# FPGA_C.net
KiCad netlist of a schematic drawn in Altium Designer
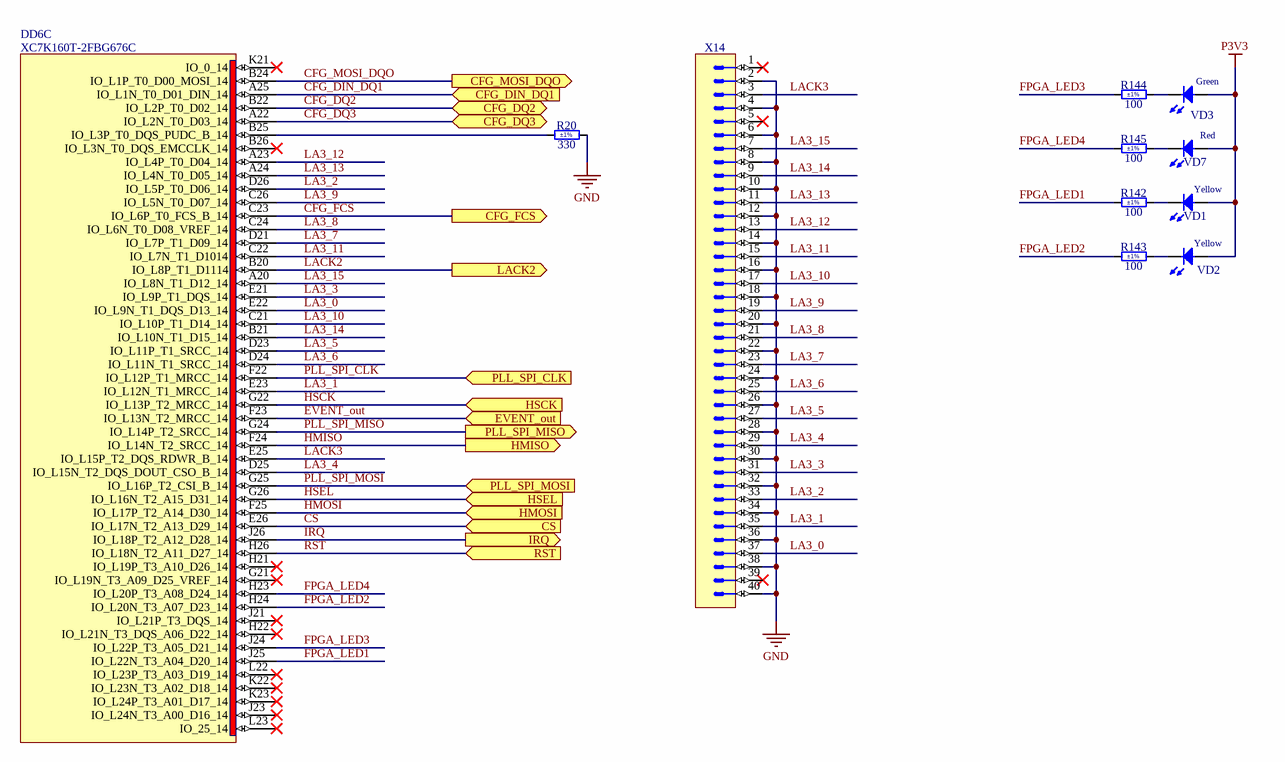
[diagram p0: FPGA_C.SchDoc]

(export (version "E")
  (design (tool "Eeschema 10.0.6"))
  (components
    (comp (ref "DD6")
      (value "XC7K160T-2FBG676C")
      (footprint "BGA676C100P26X26_2700X2700X254")
      (description "KINTEX-7, FPGA, 676-Ball BGA, Pb-Free")
      (fields (field (name "MANUFACTURER") "XILINX") (field (name "AUTHOR") "CERN DEM BC"))
      (libsource (lib "ICs And Semiconductors") (part "XC7K160T-xFBG676"))
    )
    (comp (ref "R20")
      (value "330")
      (footprint "RESC2012X60N")
      (description "Resistor - 1%")
      (fields
        (field (name "TOLERANCE") "±1%")
        (field (name "PART NUMBER") "R0805_330R_1%_0.125W_100PPM")
        (field (name "POWER") "0.125W")
        (field (name "AUTHOR") "CERN DEM JLC")
      )
      (libsource (lib "Resistors") (part "Resistor - 1%"))
    )
    (comp (ref "R142")
      (value "100")
      (footprint "RESC2012X60N")
      (description "Resistor - 1%")
      (fields
        (field (name "TOLERANCE") "±1%")
        (field (name "PART NUMBER") "R0805_100R_1%_0.125W_100PPM")
        (field (name "POWER") "0.125W")
        (field (name "AUTHOR") "CERN DEM JLC")
      )
      (libsource (lib "Resistors") (part "Resistor - 1%"))
    )
    (comp (ref "R143")
      (value "100")
      (footprint "RESC2012X60N")
      (description "Resistor - 1%")
      (fields
        (field (name "TOLERANCE") "±1%")
        (field (name "PART NUMBER") "R0805_100R_1%_0.125W_100PPM")
        (field (name "POWER") "0.125W")
        (field (name "AUTHOR") "CERN DEM JLC")
      )
      (libsource (lib "Resistors") (part "Resistor - 1%"))
    )
    (comp (ref "R144")
      (value "100")
      (footprint "RESC2012X60N")
      (description "Resistor - 1%")
      (fields
        (field (name "TOLERANCE") "±1%")
        (field (name "PART NUMBER") "R0805_100R_1%_0.125W_100PPM")
        (field (name "POWER") "0.125W")
        (field (name "AUTHOR") "CERN DEM JLC")
      )
      (libsource (lib "Resistors") (part "Resistor - 1%"))
    )
    (comp (ref "R145")
      (value "100")
      (footprint "RESC2012X60N")
      (description "Resistor - 1%")
      (fields
        (field (name "TOLERANCE") "±1%")
        (field (name "PART NUMBER") "R0805_100R_1%_0.125W_100PPM")
        (field (name "POWER") "0.125W")
        (field (name "AUTHOR") "CERN DEM JLC")
      )
      (libsource (lib "Resistors") (part "Resistor - 1%"))
    )
    (comp (ref "VD1")
      (value "Yellow")
      (footprint "LED_KINGBRIGHT_KPT-2012YC")
      (description "LED Yellow 1C 2A")
      (fields
        (field (name "PART NUMBER") "LED_KINGBRIGHT_KPT-2012YC")
        (field (name "MANUFACTURER") "KINGBRIGHT")
        (field (name "AUTHOR") "CERN DEM JMW")
      )
      (libsource (lib "ICs And Semiconductors") (part "LED Yellow 1C 2A"))
    )
    (comp (ref "VD2")
      (value "Yellow")
      (footprint "LED_KINGBRIGHT_KPT-2012YC")
      (description "LED Yellow 1C 2A")
      (fields
        (field (name "PART NUMBER") "LED_KINGBRIGHT_KPT-2012YC")
        (field (name "MANUFACTURER") "KINGBRIGHT")
        (field (name "AUTHOR") "CERN DEM JMW")
      )
      (libsource (lib "ICs And Semiconductors") (part "LED Yellow 1C 2A"))
    )
    (comp (ref "VD3")
      (value "Green")
      (footprint "LED_KINGBRIGHT_KP-2012LSGC")
      (description "LED Green 1C 2A")
      (fields
        (field (name "PART NUMBER") "LED_KINGBRIGHT_KP-2012LSGC")
        (field (name "MANUFACTURER") "KINGBRIGHT")
        (field (name "AUTHOR") "CERN DEM BC")
      )
      (libsource (lib "ICs And Semiconductors") (part "LED Green 1C 2A"))
    )
    (comp (ref "VD7")
      (value "Red")
      (footprint "LED_KINGBRIGHT_KPT-2012SURCK")
      (description "LED Red 1C 2A")
      (fields
        (field (name "PART NUMBER") "LED_KINGBRIGHT_KPT-2012SURCK")
        (field (name "MANUFACTURER") "KINGBRIGHT")
        (field (name "AUTHOR") "CERN DEM BC")
      )
      (libsource (lib "ICs And Semiconductors") (part "LED Red 1C 2A"))
    )
    (comp (ref "X14")
      (value "~")
      (footprint "CONNFLY_DS1013-40SSIB1-B-0")
      (description "Connector 40 Male")
      (fields
        (field (name "PART NUMBER") "CONNFLY_DS1013-40SSIB1-B-0")
        (field (name "MANUFACTURER") "CONNFLY")
        (field (name "AUTHOR") "CERN DEM HF")
      )
      (libsource (lib "Connectors") (part "Connector 40 Male"))
    )
  )
  (nets
    (net (code "1") (name "/CFG_DIN_DQ1") (class "Default")
      (node (ref "DD6") (pin "A25") (pinfunction "IO_L1N_T0_D01_DIN_14_A25") (pintype "bidirectional"))
    )
    (net (code "2") (name "/CFG_DQ2") (class "Default")
      (node (ref "DD6") (pin "B22") (pinfunction "IO_L2P_T0_D02_14_B22") (pintype "bidirectional"))
    )
    (net (code "3") (name "/CFG_DQ3") (class "Default")
      (node (ref "DD6") (pin "A22") (pinfunction "IO_L2N_T0_D03_14_A22") (pintype "bidirectional"))
    )
    (net (code "4") (name "/CFG_FCS") (class "Default")
      (node (ref "DD6") (pin "C23") (pinfunction "IO_L6P_T0_FCS_B_14_C23") (pintype "bidirectional"))
    )
    (net (code "5") (name "/CFG_MOSI_DQO") (class "Default")
      (node (ref "DD6") (pin "B24") (pinfunction "IO_L1P_T0_D00_MOSI_14_B24") (pintype "bidirectional"))
    )
    (net (code "6") (name "/CS") (class "Default")
      (node (ref "DD6") (pin "E26") (pinfunction "IO_L17N_T2_A13_D29_14_E26") (pintype "bidirectional"))
    )
    (net (code "7") (name "/EVENT_out") (class "Default")
      (node (ref "DD6") (pin "F23") (pinfunction "IO_L13N_T2_MRCC_14_F23") (pintype "bidirectional"))
    )
    (net (code "8") (name "/FPGA_LED1") (class "Default")
      (node (ref "DD6") (pin "J25") (pinfunction "IO_L22N_T3_A04_D20_14_J25") (pintype "bidirectional"))
      (node (ref "R142") (pin "1") (pinfunction "1_1") (pintype "passive"))
    )
    (net (code "9") (name "/FPGA_LED2") (class "Default")
      (node (ref "DD6") (pin "H24") (pinfunction "IO_L20N_T3_A07_D23_14_H24") (pintype "bidirectional"))
      (node (ref "R143") (pin "1") (pinfunction "1_1") (pintype "passive"))
    )
    (net (code "10") (name "/FPGA_LED3") (class "Default")
      (node (ref "DD6") (pin "J24") (pinfunction "IO_L22P_T3_A05_D21_14_J24") (pintype "bidirectional"))
      (node (ref "R144") (pin "1") (pinfunction "1_1") (pintype "passive"))
    )
    (net (code "11") (name "/FPGA_LED4") (class "Default")
      (node (ref "DD6") (pin "H23") (pinfunction "IO_L20P_T3_A08_D24_14_H23") (pintype "bidirectional"))
      (node (ref "R145") (pin "1") (pinfunction "1_1") (pintype "passive"))
    )
    (net (code "12") (name "/HMISO") (class "Default")
      (node (ref "DD6") (pin "F24") (pinfunction "IO_L14N_T2_SRCC_14_F24") (pintype "bidirectional"))
    )
    (net (code "13") (name "/HMOSI") (class "Default")
      (node (ref "DD6") (pin "F25") (pinfunction "IO_L17P_T2_A14_D30_14_F25") (pintype "bidirectional"))
    )
    (net (code "14") (name "/HSCK") (class "Default")
      (node (ref "DD6") (pin "G22") (pinfunction "IO_L13P_T2_MRCC_14_G22") (pintype "bidirectional"))
    )
    (net (code "15") (name "/HSEL") (class "Default")
      (node (ref "DD6") (pin "G26") (pinfunction "IO_L16N_T2_A15_D31_14_G26") (pintype "bidirectional"))
    )
    (net (code "16") (name "/IRQ") (class "Default")
      (node (ref "DD6") (pin "J26") (pinfunction "IO_L18P_T2_A12_D28_14_J26") (pintype "bidirectional"))
    )
    (net (code "17") (name "/LA3_0") (class "Default")
      (node (ref "DD6") (pin "E22") (pinfunction "IO_L9N_T1_DQS_D13_14_E22") (pintype "bidirectional"))
      (node (ref "X14") (pin "37") (pinfunction "37_37") (pintype "bidirectional"))
    )
    (net (code "18") (name "/LA3_1") (class "Default")
      (node (ref "DD6") (pin "E23") (pinfunction "IO_L12N_T1_MRCC_14_E23") (pintype "bidirectional"))
      (node (ref "X14") (pin "35") (pinfunction "35_35") (pintype "bidirectional"))
    )
    (net (code "19") (name "/LA3_2") (class "Default")
      (node (ref "DD6") (pin "D26") (pinfunction "IO_L5P_T0_D06_14_D26") (pintype "bidirectional"))
      (node (ref "X14") (pin "33") (pinfunction "33_33") (pintype "bidirectional"))
    )
    (net (code "20") (name "/LA3_3") (class "Default")
      (node (ref "DD6") (pin "E21") (pinfunction "IO_L9P_T1_DQS_14_E21") (pintype "bidirectional"))
      (node (ref "X14") (pin "31") (pinfunction "31_31") (pintype "bidirectional"))
    )
    (net (code "21") (name "/LA3_4") (class "Default")
      (node (ref "DD6") (pin "D25") (pinfunction "IO_L15N_T2_DQS_DOUT_CSO_B_14_D25") (pintype "bidirectional"))
      (node (ref "X14") (pin "29") (pinfunction "29_29") (pintype "bidirectional"))
    )
    (net (code "22") (name "/LA3_5") (class "Default")
      (node (ref "DD6") (pin "D23") (pinfunction "IO_L11P_T1_SRCC_14_D23") (pintype "bidirectional"))
      (node (ref "X14") (pin "27") (pinfunction "27_27") (pintype "bidirectional"))
    )
    (net (code "23") (name "/LA3_6") (class "Default")
      (node (ref "DD6") (pin "D24") (pinfunction "IO_L11N_T1_SRCC_14_D24") (pintype "bidirectional"))
      (node (ref "X14") (pin "25") (pinfunction "25_25") (pintype "bidirectional"))
    )
    (net (code "24") (name "/LA3_7") (class "Default")
      (node (ref "DD6") (pin "D21") (pinfunction "IO_L7P_T1_D09_14_D21") (pintype "bidirectional"))
      (node (ref "X14") (pin "23") (pinfunction "23_23") (pintype "bidirectional"))
    )
    (net (code "25") (name "/LA3_8") (class "Default")
      (node (ref "DD6") (pin "C24") (pinfunction "IO_L6N_T0_D08_VREF_14_C24") (pintype "bidirectional"))
      (node (ref "X14") (pin "21") (pinfunction "21_21") (pintype "bidirectional"))
    )
    (net (code "26") (name "/LA3_9") (class "Default")
      (node (ref "DD6") (pin "C26") (pinfunction "IO_L5N_T0_D07_14_C26") (pintype "bidirectional"))
      (node (ref "X14") (pin "19") (pinfunction "19_19") (pintype "bidirectional"))
    )
    (net (code "27") (name "/LA3_10") (class "Default")
      (node (ref "DD6") (pin "C21") (pinfunction "IO_L10P_T1_D14_14_C21") (pintype "bidirectional"))
      (node (ref "X14") (pin "17") (pinfunction "17_17") (pintype "bidirectional"))
    )
    (net (code "28") (name "/LA3_11") (class "Default")
      (node (ref "DD6") (pin "C22") (pinfunction "IO_L7N_T1_D1014_C22") (pintype "bidirectional"))
      (node (ref "X14") (pin "15") (pinfunction "15_15") (pintype "bidirectional"))
    )
    (net (code "29") (name "/LA3_12") (class "Default")
      (node (ref "DD6") (pin "A23") (pinfunction "IO_L4P_T0_D04_14_A23") (pintype "bidirectional"))
      (node (ref "X14") (pin "13") (pinfunction "13_13") (pintype "bidirectional"))
    )
    (net (code "30") (name "/LA3_13") (class "Default")
      (node (ref "DD6") (pin "A24") (pinfunction "IO_L4N_T0_D05_14_A24") (pintype "bidirectional"))
      (node (ref "X14") (pin "11") (pinfunction "11_11") (pintype "bidirectional"))
    )
    (net (code "31") (name "/LA3_14") (class "Default")
      (node (ref "DD6") (pin "B21") (pinfunction "IO_L10N_T1_D15_14_B21") (pintype "bidirectional"))
      (node (ref "X14") (pin "9") (pinfunction "9_9") (pintype "bidirectional"))
    )
    (net (code "32") (name "/LA3_15") (class "Default")
      (node (ref "DD6") (pin "A20") (pinfunction "IO_L8N_T1_D12_14_A20") (pintype "bidirectional"))
      (node (ref "X14") (pin "7") (pinfunction "7_7") (pintype "bidirectional"))
    )
    (net (code "33") (name "/LACK2") (class "Default")
      (node (ref "DD6") (pin "B20") (pinfunction "IO_L8P_T1_D1114_B20") (pintype "bidirectional"))
    )
    (net (code "34") (name "/LACK3") (class "Default")
      (node (ref "DD6") (pin "E25") (pinfunction "IO_L15P_T2_DQS_RDWR_B_14_E25") (pintype "bidirectional"))
      (node (ref "X14") (pin "3") (pinfunction "3_3") (pintype "bidirectional"))
    )
    (net (code "35") (name "/PLL_SPI_CLK") (class "Default")
      (node (ref "DD6") (pin "F22") (pinfunction "IO_L12P_T1_MRCC_14_F22") (pintype "bidirectional"))
    )
    (net (code "36") (name "/PLL_SPI_MISO") (class "Default")
      (node (ref "DD6") (pin "G24") (pinfunction "IO_L14P_T2_SRCC_14_G24") (pintype "bidirectional"))
    )
    (net (code "37") (name "/PLL_SPI_MOSI") (class "Default")
      (node (ref "DD6") (pin "G25") (pinfunction "IO_L16P_T2_CSI_B_14_G25") (pintype "bidirectional"))
    )
    (net (code "38") (name "/RST") (class "Default")
      (node (ref "DD6") (pin "H26") (pinfunction "IO_L18N_T2_A11_D27_14_H26") (pintype "bidirectional"))
    )
    (net (code "39") (name "GND") (class "Default")
      (node (ref "R20") (pin "2") (pinfunction "2_2") (pintype "passive"))
      (node (ref "X14") (pin "10") (pinfunction "10_10") (pintype "bidirectional"))
      (node (ref "X14") (pin "12") (pinfunction "12_12") (pintype "bidirectional"))
      (node (ref "X14") (pin "14") (pinfunction "14_14") (pintype "bidirectional"))
      (node (ref "X14") (pin "16") (pinfunction "16_16") (pintype "bidirectional"))
      (node (ref "X14") (pin "18") (pinfunction "18_18") (pintype "bidirectional"))
      (node (ref "X14") (pin "2") (pinfunction "2_2") (pintype "bidirectional"))
      (node (ref "X14") (pin "20") (pinfunction "20_20") (pintype "bidirectional"))
      (node (ref "X14") (pin "22") (pinfunction "22_22") (pintype "bidirectional"))
      (node (ref "X14") (pin "24") (pinfunction "24_24") (pintype "bidirectional"))
      (node (ref "X14") (pin "26") (pinfunction "26_26") (pintype "bidirectional"))
      (node (ref "X14") (pin "28") (pinfunction "28_28") (pintype "bidirectional"))
      (node (ref "X14") (pin "30") (pinfunction "30_30") (pintype "bidirectional"))
      (node (ref "X14") (pin "32") (pinfunction "32_32") (pintype "bidirectional"))
      (node (ref "X14") (pin "34") (pinfunction "34_34") (pintype "bidirectional"))
      (node (ref "X14") (pin "36") (pinfunction "36_36") (pintype "bidirectional"))
      (node (ref "X14") (pin "38") (pinfunction "38_38") (pintype "bidirectional"))
      (node (ref "X14") (pin "4") (pinfunction "4_4") (pintype "bidirectional"))
      (node (ref "X14") (pin "40") (pinfunction "40_40") (pintype "bidirectional"))
      (node (ref "X14") (pin "6") (pinfunction "6_6") (pintype "bidirectional"))
      (node (ref "X14") (pin "8") (pinfunction "8_8") (pintype "bidirectional"))
    )
    (net (code "40") (name "Net-(DD6C-IO_L3P_T0_DQS_PUDC_B_14)") (class "Default")
      (node (ref "DD6") (pin "B25") (pinfunction "IO_L3P_T0_DQS_PUDC_B_14_B25") (pintype "bidirectional"))
      (node (ref "R20") (pin "1") (pinfunction "1_1") (pintype "passive"))
    )
    (net (code "41") (name "Net-(VD1-C)") (class "Default")
      (node (ref "R142") (pin "2") (pinfunction "2_2") (pintype "passive"))
      (node (ref "VD1") (pin "1") (pinfunction "C_1") (pintype "passive"))
    )
    (net (code "42") (name "Net-(VD2-C)") (class "Default")
      (node (ref "R143") (pin "2") (pinfunction "2_2") (pintype "passive"))
      (node (ref "VD2") (pin "1") (pinfunction "C_1") (pintype "passive"))
    )
    (net (code "43") (name "Net-(VD3-C)") (class "Default")
      (node (ref "R144") (pin "2") (pinfunction "2_2") (pintype "passive"))
      (node (ref "VD3") (pin "1") (pinfunction "C_1") (pintype "passive"))
    )
    (net (code "44") (name "Net-(VD7-C)") (class "Default")
      (node (ref "R145") (pin "2") (pinfunction "2_2") (pintype "passive"))
      (node (ref "VD7") (pin "1") (pinfunction "C_1") (pintype "passive"))
    )
    (net (code "45") (name "P3V3") (class "Default")
      (node (ref "VD1") (pin "2") (pinfunction "A_2") (pintype "passive"))
      (node (ref "VD2") (pin "2") (pinfunction "A_2") (pintype "passive"))
      (node (ref "VD3") (pin "2") (pinfunction "A_2") (pintype "passive"))
      (node (ref "VD7") (pin "2") (pinfunction "A_2") (pintype "passive"))
    )
    (net (code "46") (name "unconnected-(DD6C-IO_0_14-PadK21)") (class "Default")
      (node (ref "DD6") (pin "K21") (pinfunction "IO_0_14_K21") (pintype "bidirectional+no_connect"))
    )
    (net (code "47") (name "unconnected-(DD6C-IO_25_14-PadL23)") (class "Default")
      (node (ref "DD6") (pin "L23") (pinfunction "IO_25_14_L23") (pintype "bidirectional+no_connect"))
    )
    (net (code "48") (name "unconnected-(DD6C-IO_L3N_T0_DQS_EMCCLK_14-PadB26)") (class "Default")
      (node (ref "DD6") (pin "B26") (pinfunction "IO_L3N_T0_DQS_EMCCLK_14_B26") (pintype "bidirectional+no_connect"))
    )
    (net (code "49") (name "unconnected-(DD6C-IO_L19N_T3_A09_D25_VREF_14-PadG21)") (class "Default")
      (node (ref "DD6") (pin "G21") (pinfunction "IO_L19N_T3_A09_D25_VREF_14_G21") (pintype "bidirectional+no_connect"))
    )
    (net (code "50") (name "unconnected-(DD6C-IO_L19P_T3_A10_D26_14-PadH21)") (class "Default")
      (node (ref "DD6") (pin "H21") (pinfunction "IO_L19P_T3_A10_D26_14_H21") (pintype "bidirectional+no_connect"))
    )
    (net (code "51") (name "unconnected-(DD6C-IO_L21N_T3_DQS_A06_D22_14-PadH22)") (class "Default")
      (node (ref "DD6") (pin "H22") (pinfunction "IO_L21N_T3_DQS_A06_D22_14_H22") (pintype "bidirectional+no_connect"))
    )
    (net (code "52") (name "unconnected-(DD6C-IO_L21P_T3_DQS_14-PadJ21)") (class "Default")
      (node (ref "DD6") (pin "J21") (pinfunction "IO_L21P_T3_DQS_14_J21") (pintype "bidirectional+no_connect"))
    )
    (net (code "53") (name "unconnected-(DD6C-IO_L23N_T3_A02_D18_14-PadK22)") (class "Default")
      (node (ref "DD6") (pin "K22") (pinfunction "IO_L23N_T3_A02_D18_14_K22") (pintype "bidirectional+no_connect"))
    )
    (net (code "54") (name "unconnected-(DD6C-IO_L23P_T3_A03_D19_14-PadL22)") (class "Default")
      (node (ref "DD6") (pin "L22") (pinfunction "IO_L23P_T3_A03_D19_14_L22") (pintype "bidirectional+no_connect"))
    )
    (net (code "55") (name "unconnected-(DD6C-IO_L24N_T3_A00_D16_14-PadJ23)") (class "Default")
      (node (ref "DD6") (pin "J23") (pinfunction "IO_L24N_T3_A00_D16_14_J23") (pintype "bidirectional+no_connect"))
    )
    (net (code "56") (name "unconnected-(DD6C-IO_L24P_T3_A01_D17_14-PadK23)") (class "Default")
      (node (ref "DD6") (pin "K23") (pinfunction "IO_L24P_T3_A01_D17_14_K23") (pintype "bidirectional+no_connect"))
    )
    (net (code "57") (name "unconnected-(X14-Pad1)") (class "Default")
      (node (ref "X14") (pin "1") (pinfunction "1_1") (pintype "bidirectional+no_connect"))
    )
    (net (code "58") (name "unconnected-(X14-Pad5)") (class "Default")
      (node (ref "X14") (pin "5") (pinfunction "5_5") (pintype "bidirectional+no_connect"))
    )
    (net (code "59") (name "unconnected-(X14-Pad39)") (class "Default")
      (node (ref "X14") (pin "39") (pinfunction "39_39") (pintype "bidirectional+no_connect"))
    )
  )
)
